# CAN.net
KiCad netlist of a schematic drawn in Altium Designer
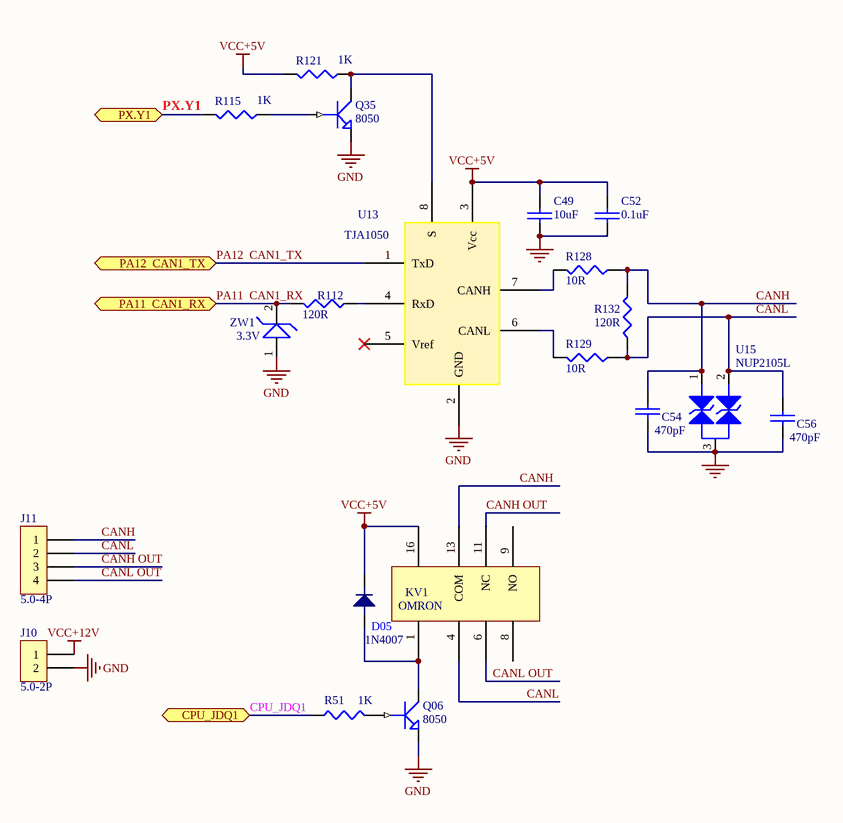
[diagram p0: CAN.SchDoc]

(export (version "E")
  (design (tool "Eeschema 10.0.6"))
  (components
    (comp (ref "C49")
      (value "10uF")
      (footprint "0805")
      (description "0805陶瓷贴片电容")
      (libsource (lib "INSPUR_PCB") (part "CAP-0805"))
    )
    (comp (ref "C52")
      (value "0.1uF")
      (footprint "0603")
      (description "0603陶瓷贴片电容")
      (libsource (lib "INSPUR_PCB") (part "CAP-0603"))
    )
    (comp (ref "C54")
      (value "470pF")
      (footprint "0603")
      (description "0603陶瓷贴片电容")
      (libsource (lib "INSPUR_PCB") (part "CAP-0603"))
    )
    (comp (ref "C56")
      (value "470pF")
      (footprint "0603")
      (description "0603陶瓷贴片电容")
      (libsource (lib "INSPUR_PCB") (part "CAP-0603"))
    )
    (comp (ref "D05")
      (value "1N4007")
      (footprint "DO-214AC(SMA)")
      (description "1A整流二极管")
      (libsource (lib "mylib") (part "1N4007"))
    )
    (comp (ref "J10")
      (value "5.0-2P")
      (footprint "5.0-2")
      (description "WJ301V-5.00-2P")
      (libsource (lib "INSPUR_PCB") (part "5.0-2P"))
    )
    (comp (ref "J11")
      (value "5.0-4P")
      (footprint "5.0-4")
      (description "WJ301V-5.00-4P")
      (libsource (lib "INSPUR_PCB") (part "5.0-4P"))
    )
    (comp (ref "KV1")
      (value "OMRON")
      (footprint "KV")
      (description "omron G5V-2 12VDC")
      (libsource (lib "INSPUR_SCH") (part "OMRON"))
    )
    (comp (ref "Q06") (value "8050") (footprint "SOT-23") (libsource (lib "INSPUR_SCH") (part "NPN1")))
    (comp (ref "Q35")
      (value "8050")
      (footprint "SOT-23")
      (description "8050 NPN型三极管")
      (libsource (lib "INSPUR_PCB") (part "8050"))
    )
    (comp (ref "R51") (value "1K") (footprint "0603") (libsource (lib "INSPUR_SCH") (part "RES1")))
    (comp (ref "R112")
      (value "120R")
      (footprint "0603")
      (description "陶瓷贴片电阻0603封装")
      (libsource (lib "INSPUR_PCB") (part "RES-0603"))
    )
    (comp (ref "R115")
      (value "1K")
      (footprint "0603")
      (description "陶瓷贴片电阻0603封装")
      (libsource (lib "INSPUR_PCB") (part "RES-0603"))
    )
    (comp (ref "R121")
      (value "1K")
      (footprint "0603")
      (description "陶瓷贴片电阻0603封装")
      (libsource (lib "INSPUR_PCB") (part "RES-0603"))
    )
    (comp (ref "R128")
      (value "10R")
      (footprint "0603")
      (description "陶瓷贴片电阻0603封装")
      (libsource (lib "INSPUR_PCB") (part "RES-0603"))
    )
    (comp (ref "R129")
      (value "10R")
      (footprint "0603")
      (description "陶瓷贴片电阻0603封装")
      (libsource (lib "INSPUR_PCB") (part "RES-0603"))
    )
    (comp (ref "R132")
      (value "120R")
      (footprint "0603")
      (description "陶瓷贴片电阻0603封装")
      (libsource (lib "INSPUR_PCB") (part "RES-0603"))
    )
    (comp (ref "U13")
      (value "TJA1050")
      (footprint "SO-8")
      (description "TJA1050   CAN芯片")
      (libsource (lib "INSPUR_PCB") (part "TJA1050"))
    )
    (comp (ref "U15")
      (value "NUP2105L")
      (footprint "SOT-23")
      (description "NUP2105L  TVS三极管")
      (libsource (lib "INSPUR_PCB") (part "NUP2105L"))
    )
    (comp (ref "ZW1")
      (value "3.3V")
      (footprint "LL-34")
      (description "ZMM3V3")
      (libsource (lib "INSPUR_PCB") (part "3.3V"))
    )
  )
  (nets
    (net (code "1") (name "/CANH") (class "Default")
      (node (ref "C54") (pin "2") (pinfunction "2_2") (pintype "passive"))
      (node (ref "J11") (pin "1") (pinfunction "1_1") (pintype "passive"))
      (node (ref "KV1") (pin "13") (pinfunction "COM_13") (pintype "passive"))
      (node (ref "R128") (pin "1") (pinfunction "1_1") (pintype "passive"))
      (node (ref "R132") (pin "2") (pinfunction "2_2") (pintype "passive"))
      (node (ref "U15") (pin "1") (pintype "passive"))
    )
    (net (code "2") (name "/CANH OUT") (class "Default")
      (node (ref "J11") (pin "3") (pinfunction "3_3") (pintype "passive"))
      (node (ref "KV1") (pin "11") (pinfunction "NC_11") (pintype "passive"))
    )
    (net (code "3") (name "/CANL") (class "Default")
      (node (ref "C56") (pin "2") (pinfunction "2_2") (pintype "passive"))
      (node (ref "J11") (pin "2") (pinfunction "2_2") (pintype "passive"))
      (node (ref "KV1") (pin "4") (pinfunction "1_4") (pintype "passive"))
      (node (ref "R129") (pin "1") (pinfunction "1_1") (pintype "passive"))
      (node (ref "R132") (pin "1") (pinfunction "1_1") (pintype "passive"))
      (node (ref "U15") (pin "2") (pinfunction "K_2") (pintype "passive"))
    )
    (net (code "4") (name "/CANL OUT") (class "Default")
      (node (ref "J11") (pin "4") (pinfunction "4_4") (pintype "passive"))
      (node (ref "KV1") (pin "6") (pinfunction "2_6") (pintype "passive"))
    )
    (net (code "5") (name "/CPU_JDQ1") (class "Default")
      (node (ref "R51") (pin "1") (pinfunction "1_1") (pintype "passive"))
    )
    (net (code "6") (name "/PA11  CAN1_RX") (class "Default")
      (node (ref "R112") (pin "2") (pinfunction "2_2") (pintype "passive"))
      (node (ref "ZW1") (pin "2") (pintype "passive"))
    )
    (net (code "7") (name "/PA12  CAN1_TX") (class "Default")
      (node (ref "U13") (pin "1") (pinfunction "TxD_1") (pintype "passive"))
    )
    (net (code "8") (name "/PX.Y1") (class "Default")
      (node (ref "R115") (pin "2") (pinfunction "2_2") (pintype "passive"))
    )
    (net (code "9") (name "GND") (class "Default")
      (node (ref "C49") (pin "2") (pinfunction "2_2") (pintype "passive"))
      (node (ref "C52") (pin "1") (pinfunction "1_1") (pintype "passive"))
      (node (ref "C54") (pin "1") (pinfunction "1_1") (pintype "passive"))
      (node (ref "C56") (pin "1") (pinfunction "1_1") (pintype "passive"))
      (node (ref "J10") (pin "2") (pinfunction "2_2") (pintype "passive"))
      (node (ref "Q06") (pin "2") (pinfunction "E_2") (pintype "passive"))
      (node (ref "Q35") (pin "2") (pinfunction "E_2") (pintype "passive"))
      (node (ref "U13") (pin "2") (pinfunction "GND_2") (pintype "passive"))
      (node (ref "U15") (pin "3") (pintype "passive"))
      (node (ref "ZW1") (pin "1") (pintype "passive"))
    )
    (net (code "10") (name "Net-(Q06-B)") (class "Default")
      (node (ref "Q06") (pin "1") (pinfunction "B_1") (pintype "input"))
      (node (ref "R51") (pin "2") (pinfunction "2_2") (pintype "passive"))
    )
    (net (code "11") (name "Net-(Q06-C)") (class "Default")
      (node (ref "D05") (pin "1") (pintype "passive"))
      (node (ref "KV1") (pin "1") (pintype "passive"))
      (node (ref "Q06") (pin "3") (pinfunction "C_3") (pintype "passive"))
    )
    (net (code "12") (name "Net-(Q35-B)") (class "Default")
      (node (ref "Q35") (pin "1") (pinfunction "B_1") (pintype "input"))
      (node (ref "R115") (pin "1") (pinfunction "1_1") (pintype "passive"))
    )
    (net (code "13") (name "Net-(Q35-C)") (class "Default")
      (node (ref "Q35") (pin "3") (pinfunction "C_3") (pintype "passive"))
      (node (ref "R121") (pin "1") (pinfunction "1_1") (pintype "passive"))
      (node (ref "U13") (pin "8") (pinfunction "S_8") (pintype "passive"))
    )
    (net (code "14") (name "Net-(U13-CANH)") (class "Default")
      (node (ref "R128") (pin "2") (pinfunction "2_2") (pintype "passive"))
      (node (ref "U13") (pin "7") (pinfunction "CANH_7") (pintype "passive"))
    )
    (net (code "15") (name "Net-(U13-CANL)") (class "Default")
      (node (ref "R129") (pin "2") (pinfunction "2_2") (pintype "passive"))
      (node (ref "U13") (pin "6") (pinfunction "CANL_6") (pintype "passive"))
    )
    (net (code "16") (name "Net-(U13-RxD)") (class "Default")
      (node (ref "R112") (pin "1") (pinfunction "1_1") (pintype "passive"))
      (node (ref "U13") (pin "4") (pinfunction "RxD_4") (pintype "passive"))
    )
    (net (code "17") (name "VCC+5V") (class "Default")
      (node (ref "C49") (pin "1") (pinfunction "1_1") (pintype "passive"))
      (node (ref "C52") (pin "2") (pinfunction "2_2") (pintype "passive"))
      (node (ref "D05") (pin "2") (pintype "passive"))
      (node (ref "KV1") (pin "16") (pintype "passive"))
      (node (ref "R121") (pin "2") (pinfunction "2_2") (pintype "passive"))
      (node (ref "U13") (pin "3") (pinfunction "Vcc_3") (pintype "passive"))
    )
    (net (code "18") (name "VCC+12V") (class "Default")
      (node (ref "J10") (pin "1") (pinfunction "1_1") (pintype "passive"))
    )
    (net (code "19") (name "unconnected-(KV1-3-Pad8)") (class "Default")
      (node (ref "KV1") (pin "8") (pinfunction "3_8") (pintype "passive"))
    )
    (net (code "20") (name "unconnected-(KV1-NO-Pad9)") (class "Default")
      (node (ref "KV1") (pin "9") (pinfunction "NO_9") (pintype "passive"))
    )
    (net (code "21") (name "unconnected-(U13-Vref-Pad5)") (class "Default")
      (node (ref "U13") (pin "5") (pinfunction "Vref_5") (pintype "passive+no_connect"))
    )
  )
)
